# Button_LED_Layout_RTK_Express.net
KiCad netlist of a schematic drawn in EAGLE
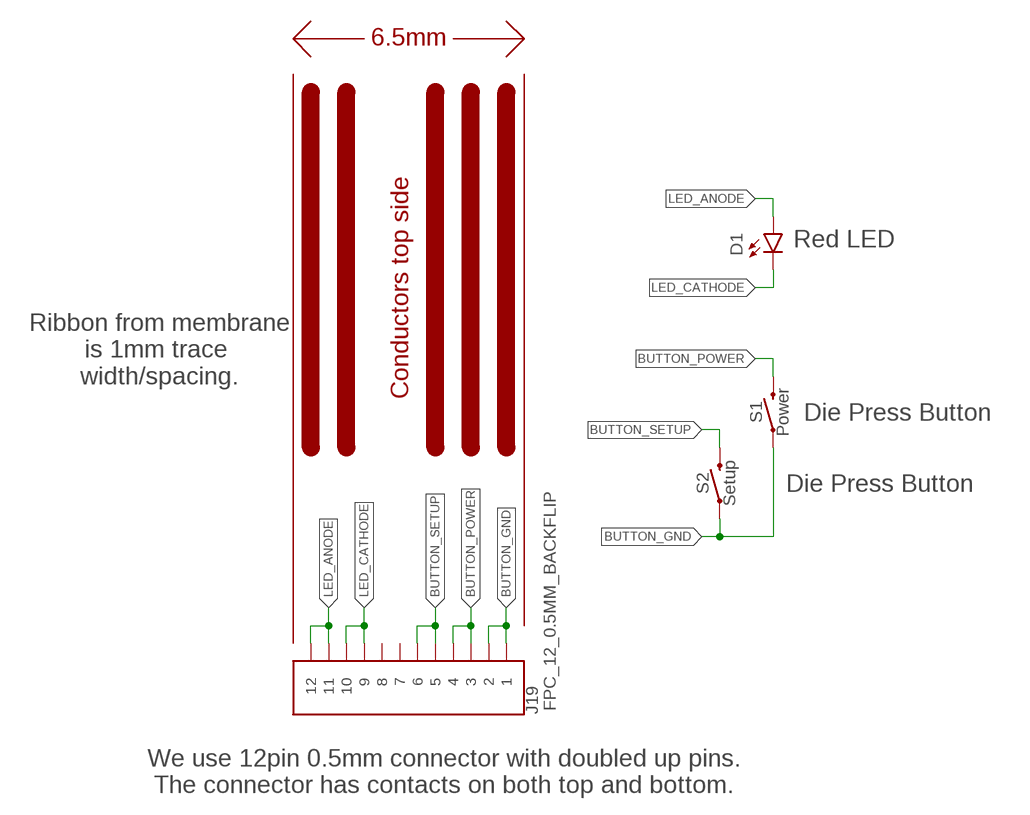
[diagram p0: schematic, sheet 1]

(export (version "E")
  (design (tool "Eeschema 10.0.6"))
  (components
    (comp (ref "D1")
      (value "LED5MM")
      (footprint "eagle-import:LED_5MM")
      (libsource (lib "eagle-import") (part "LED5MM"))
    )
    (comp (ref "J19")
      (value "FPC_12_0.5MM_BACKFLIP")
      (footprint "eagle-import:FPC_12_DOUBLESIDED_BACKFLIP")
      (libsource (lib "eagle-import") (part "FPC_12_0.5MM_BACKFLIP"))
    )
    (comp (ref "S1")
      (value "Power")
      (footprint "eagle-import:TACTILE_SWITCH_PTH_6.0MM")
      (libsource (lib "eagle-import") (part "MOMENTARY-SWITCH-SPST-PTH-6.0MM"))
    )
    (comp (ref "S2")
      (value "Setup")
      (footprint "eagle-import:TACTILE_SWITCH_PTH_6.0MM")
      (libsource (lib "eagle-import") (part "MOMENTARY-SWITCH-SPST-PTH-6.0MM"))
    )
  )
  (nets
    (net (code "1") (name "BUTTON_GND") (class "Default")
      (node (ref "J19") (pin "1") (pinfunction "1_1") (pintype "bidirectional"))
      (node (ref "J19") (pin "2") (pinfunction "2_2") (pintype "bidirectional"))
      (node (ref "S1") (pin "1") (pinfunction "1_1") (pintype "passive"))
      (node (ref "S2") (pin "1") (pinfunction "1_1") (pintype "passive"))
    )
    (net (code "2") (name "BUTTON_POWER") (class "Default")
      (node (ref "J19") (pin "3") (pinfunction "3_3") (pintype "bidirectional"))
      (node (ref "J19") (pin "4") (pinfunction "4_4") (pintype "bidirectional"))
      (node (ref "S1") (pin "3") (pinfunction "2_3") (pintype "passive"))
    )
    (net (code "3") (name "BUTTON_SETUP") (class "Default")
      (node (ref "J19") (pin "5") (pinfunction "5_5") (pintype "bidirectional"))
      (node (ref "J19") (pin "6") (pinfunction "6_6") (pintype "bidirectional"))
      (node (ref "S2") (pin "3") (pinfunction "2_3") (pintype "passive"))
    )
    (net (code "4") (name "LED_ANODE") (class "Default")
      (node (ref "D1") (pin "A") (pinfunction "A_A") (pintype "passive"))
      (node (ref "J19") (pin "11") (pinfunction "11_11") (pintype "bidirectional"))
      (node (ref "J19") (pin "12") (pinfunction "12_12") (pintype "bidirectional"))
    )
    (net (code "5") (name "LED_CATHODE") (class "Default")
      (node (ref "D1") (pin "K") (pinfunction "C_K") (pintype "passive"))
      (node (ref "J19") (pin "10") (pinfunction "10_10") (pintype "bidirectional"))
      (node (ref "J19") (pin "9") (pinfunction "9_9") (pintype "bidirectional"))
    )
    (net (code "6") (name "unconnected-(J19-Pad7)") (class "Default")
      (node (ref "J19") (pin "7") (pinfunction "7_7") (pintype "bidirectional"))
    )
    (net (code "7") (name "unconnected-(J19-Pad8)") (class "Default")
      (node (ref "J19") (pin "8") (pinfunction "8_8") (pintype "bidirectional"))
    )
  )
)
